# 16_Vibrationdriver.net
KiCad netlist of a schematic drawn in EAGLE
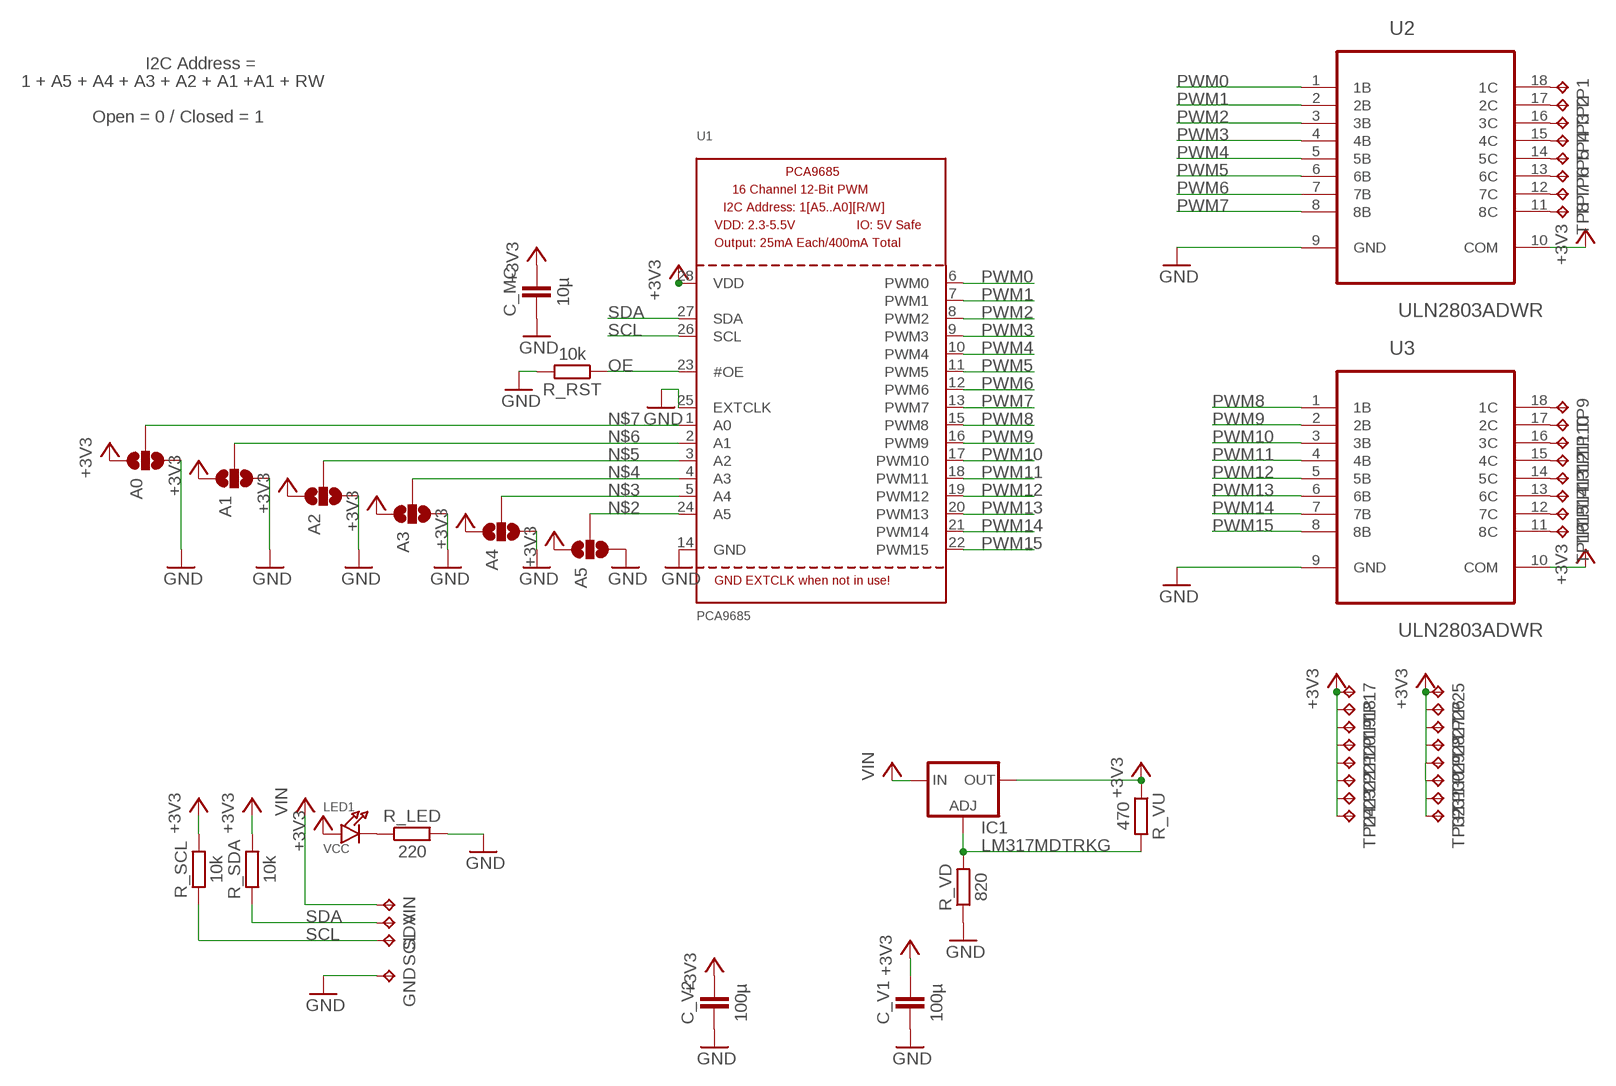
[diagram p0: schematic, sheet 1]

(export (version "E")
  (design (tool "Eeschema 10.0.6"))
  (components
    (comp (ref "A0")
      (value "SOLDERJUMPER_2WAYPASTE2&3")
      (footprint "eagle-import:SJ_3_PASTE2&3")
      (libsource (lib "eagle-import") (part "SOLDERJUMPER_2WAYPASTE2&3"))
    )
    (comp (ref "A1")
      (value "SOLDERJUMPER_2WAYPASTE2&3")
      (footprint "eagle-import:SJ_3_PASTE2&3")
      (libsource (lib "eagle-import") (part "SOLDERJUMPER_2WAYPASTE2&3"))
    )
    (comp (ref "A2")
      (value "SOLDERJUMPER_2WAYPASTE2&3")
      (footprint "eagle-import:SJ_3_PASTE2&3")
      (libsource (lib "eagle-import") (part "SOLDERJUMPER_2WAYPASTE2&3"))
    )
    (comp (ref "A3")
      (value "SOLDERJUMPER_2WAYPASTE2&3")
      (footprint "eagle-import:SJ_3_PASTE2&3")
      (libsource (lib "eagle-import") (part "SOLDERJUMPER_2WAYPASTE2&3"))
    )
    (comp (ref "A4")
      (value "SOLDERJUMPER_2WAYPASTE2&3")
      (footprint "eagle-import:SJ_3_PASTE2&3")
      (libsource (lib "eagle-import") (part "SOLDERJUMPER_2WAYPASTE2&3"))
    )
    (comp (ref "A5")
      (value "SOLDERJUMPER_2WAYPASTE2&3")
      (footprint "eagle-import:SJ_3_PASTE2&3")
      (libsource (lib "eagle-import") (part "SOLDERJUMPER_2WAYPASTE2&3"))
    )
    (comp (ref "C_MC")
      (value "10µ")
      (footprint "eagle-import:603")
      (libsource (lib "eagle-import") (part "CAPACITOR"))
    )
    (comp (ref "C_V1")
      (value "100µ")
      (footprint "eagle-import:1206")
      (libsource (lib "eagle-import") (part "CAPACITOR1206"))
    )
    (comp (ref "C_V2")
      (value "100µ")
      (footprint "eagle-import:1206")
      (libsource (lib "eagle-import") (part "CAPACITOR1206"))
    )
    (comp (ref "GND")
      (value "TPTP16SQ")
      (footprint "eagle-import:TP16SQ")
      (libsource (lib "eagle-import") (part "TPTP16SQ"))
    )
    (comp (ref "IC1")
      (value "LM317MDTRKG")
      (footprint "eagle-import:DPACK")
      (libsource (lib "eagle-import") (part "LM317?MDTRKG"))
    )
    (comp (ref "LED1")
      (value "VCC")
      (footprint "eagle-import:CHIPLED_0805")
      (libsource (lib "eagle-import") (part "LED0805"))
    )
    (comp (ref "R_LED")
      (value "220")
      (footprint "eagle-import:603")
      (libsource (lib "eagle-import") (part "RESISTOR0603"))
    )
    (comp (ref "R_RST")
      (value "10k")
      (footprint "eagle-import:603")
      (libsource (lib "eagle-import") (part "RESISTOR0603"))
    )
    (comp (ref "R_SCL")
      (value "10k")
      (footprint "eagle-import:603")
      (libsource (lib "eagle-import") (part "RESISTOR0603"))
    )
    (comp (ref "R_SDA")
      (value "10k")
      (footprint "eagle-import:603")
      (libsource (lib "eagle-import") (part "RESISTOR0603"))
    )
    (comp (ref "R_VD")
      (value "820")
      (footprint "eagle-import:603")
      (libsource (lib "eagle-import") (part "RESISTOR0603"))
    )
    (comp (ref "R_VU")
      (value "470")
      (footprint "eagle-import:603")
      (libsource (lib "eagle-import") (part "RESISTOR0603"))
    )
    (comp (ref "SCL")
      (value "TPTP16SQ")
      (footprint "eagle-import:TP16SQ")
      (libsource (lib "eagle-import") (part "TPTP16SQ"))
    )
    (comp (ref "SDA")
      (value "TPTP16SQ")
      (footprint "eagle-import:TP16SQ")
      (libsource (lib "eagle-import") (part "TPTP16SQ"))
    )
    (comp (ref "TP1")
      (value "TPTP16SQ")
      (footprint "eagle-import:TP16SQ")
      (libsource (lib "eagle-import") (part "TPTP16SQ"))
    )
    (comp (ref "TP2")
      (value "TPTP16SQ")
      (footprint "eagle-import:TP16SQ")
      (libsource (lib "eagle-import") (part "TPTP16SQ"))
    )
    (comp (ref "TP3")
      (value "TPTP16SQ")
      (footprint "eagle-import:TP16SQ")
      (libsource (lib "eagle-import") (part "TPTP16SQ"))
    )
    (comp (ref "TP4")
      (value "TPTP16SQ")
      (footprint "eagle-import:TP16SQ")
      (libsource (lib "eagle-import") (part "TPTP16SQ"))
    )
    (comp (ref "TP5")
      (value "TPTP16SQ")
      (footprint "eagle-import:TP16SQ")
      (libsource (lib "eagle-import") (part "TPTP16SQ"))
    )
    (comp (ref "TP6")
      (value "TPTP16SQ")
      (footprint "eagle-import:TP16SQ")
      (libsource (lib "eagle-import") (part "TPTP16SQ"))
    )
    (comp (ref "TP7")
      (value "TPTP16SQ")
      (footprint "eagle-import:TP16SQ")
      (libsource (lib "eagle-import") (part "TPTP16SQ"))
    )
    (comp (ref "TP8")
      (value "TPTP16SQ")
      (footprint "eagle-import:TP16SQ")
      (libsource (lib "eagle-import") (part "TPTP16SQ"))
    )
    (comp (ref "TP9")
      (value "TPTP16SQ")
      (footprint "eagle-import:TP16SQ")
      (libsource (lib "eagle-import") (part "TPTP16SQ"))
    )
    (comp (ref "TP10")
      (value "TPTP16SQ")
      (footprint "eagle-import:TP16SQ")
      (libsource (lib "eagle-import") (part "TPTP16SQ"))
    )
    (comp (ref "TP11")
      (value "TPTP16SQ")
      (footprint "eagle-import:TP16SQ")
      (libsource (lib "eagle-import") (part "TPTP16SQ"))
    )
    (comp (ref "TP12")
      (value "TPTP16SQ")
      (footprint "eagle-import:TP16SQ")
      (libsource (lib "eagle-import") (part "TPTP16SQ"))
    )
    (comp (ref "TP13")
      (value "TPTP16SQ")
      (footprint "eagle-import:TP16SQ")
      (libsource (lib "eagle-import") (part "TPTP16SQ"))
    )
    (comp (ref "TP14")
      (value "TPTP16SQ")
      (footprint "eagle-import:TP16SQ")
      (libsource (lib "eagle-import") (part "TPTP16SQ"))
    )
    (comp (ref "TP15")
      (value "TPTP16SQ")
      (footprint "eagle-import:TP16SQ")
      (libsource (lib "eagle-import") (part "TPTP16SQ"))
    )
    (comp (ref "TP16")
      (value "TPTP16SQ")
      (footprint "eagle-import:TP16SQ")
      (libsource (lib "eagle-import") (part "TPTP16SQ"))
    )
    (comp (ref "TP17")
      (value "TPTP16SQ")
      (footprint "eagle-import:TP16SQ")
      (libsource (lib "eagle-import") (part "TPTP16SQ"))
    )
    (comp (ref "TP18")
      (value "TPTP16SQ")
      (footprint "eagle-import:TP16SQ")
      (libsource (lib "eagle-import") (part "TPTP16SQ"))
    )
    (comp (ref "TP19")
      (value "TPTP16SQ")
      (footprint "eagle-import:TP16SQ")
      (libsource (lib "eagle-import") (part "TPTP16SQ"))
    )
    (comp (ref "TP20")
      (value "TPTP16SQ")
      (footprint "eagle-import:TP16SQ")
      (libsource (lib "eagle-import") (part "TPTP16SQ"))
    )
    (comp (ref "TP21")
      (value "TPTP16SQ")
      (footprint "eagle-import:TP16SQ")
      (libsource (lib "eagle-import") (part "TPTP16SQ"))
    )
    (comp (ref "TP22")
      (value "TPTP16SQ")
      (footprint "eagle-import:TP16SQ")
      (libsource (lib "eagle-import") (part "TPTP16SQ"))
    )
    (comp (ref "TP23")
      (value "TPTP16SQ")
      (footprint "eagle-import:TP16SQ")
      (libsource (lib "eagle-import") (part "TPTP16SQ"))
    )
    (comp (ref "TP24")
      (value "TPTP16SQ")
      (footprint "eagle-import:TP16SQ")
      (libsource (lib "eagle-import") (part "TPTP16SQ"))
    )
    (comp (ref "TP25")
      (value "TPTP16SQ")
      (footprint "eagle-import:TP16SQ")
      (libsource (lib "eagle-import") (part "TPTP16SQ"))
    )
    (comp (ref "TP26")
      (value "TPTP16SQ")
      (footprint "eagle-import:TP16SQ")
      (libsource (lib "eagle-import") (part "TPTP16SQ"))
    )
    (comp (ref "TP27")
      (value "TPTP16SQ")
      (footprint "eagle-import:TP16SQ")
      (libsource (lib "eagle-import") (part "TPTP16SQ"))
    )
    (comp (ref "TP28")
      (value "TPTP16SQ")
      (footprint "eagle-import:TP16SQ")
      (libsource (lib "eagle-import") (part "TPTP16SQ"))
    )
    (comp (ref "TP29")
      (value "TPTP16SQ")
      (footprint "eagle-import:TP16SQ")
      (libsource (lib "eagle-import") (part "TPTP16SQ"))
    )
    (comp (ref "TP30")
      (value "TPTP16SQ")
      (footprint "eagle-import:TP16SQ")
      (libsource (lib "eagle-import") (part "TPTP16SQ"))
    )
    (comp (ref "TP31")
      (value "TPTP16SQ")
      (footprint "eagle-import:TP16SQ")
      (libsource (lib "eagle-import") (part "TPTP16SQ"))
    )
    (comp (ref "TP32")
      (value "TPTP16SQ")
      (footprint "eagle-import:TP16SQ")
      (libsource (lib "eagle-import") (part "TPTP16SQ"))
    )
    (comp (ref "U1")
      (value "PCA9685")
      (footprint "eagle-import:TSSOP28")
      (libsource (lib "eagle-import") (part "PCA9685"))
    )
    (comp (ref "U2")
      (value "ULN2803ADWR")
      (footprint "eagle-import:SOIC127P1030X265-18N")
      (libsource (lib "eagle-import") (part "ULN2803ADWR"))
    )
    (comp (ref "U3")
      (value "ULN2803ADWR")
      (footprint "eagle-import:SOIC127P1030X265-18N")
      (libsource (lib "eagle-import") (part "ULN2803ADWR"))
    )
    (comp (ref "VIN")
      (value "TPTP16SQ")
      (footprint "eagle-import:TP16SQ")
      (libsource (lib "eagle-import") (part "TPTP16SQ"))
    )
  )
  (nets
    (net (code "1") (name "+3V3") (class "Default")
      (node (ref "A0") (pin "1") (pinfunction "1_1") (pintype "passive"))
      (node (ref "A1") (pin "1") (pinfunction "1_1") (pintype "passive"))
      (node (ref "A2") (pin "1") (pinfunction "1_1") (pintype "passive"))
      (node (ref "A3") (pin "1") (pinfunction "1_1") (pintype "passive"))
      (node (ref "A4") (pin "1") (pinfunction "1_1") (pintype "passive"))
      (node (ref "A5") (pin "1") (pinfunction "1_1") (pintype "passive"))
      (node (ref "C_MC") (pin "2") (pinfunction "2_2") (pintype "passive"))
      (node (ref "C_V1") (pin "2") (pinfunction "2_2") (pintype "passive"))
      (node (ref "C_V2") (pin "2") (pinfunction "2_2") (pintype "passive"))
      (node (ref "IC1") (pin "4") (pinfunction "OUT_4") (pintype "passive"))
      (node (ref "LED1") (pin "A") (pinfunction "A_A") (pintype "passive"))
      (node (ref "R_SCL") (pin "2") (pinfunction "2_2") (pintype "passive"))
      (node (ref "R_SDA") (pin "2") (pinfunction "2_2") (pintype "passive"))
      (node (ref "R_VU") (pin "1") (pinfunction "1_1") (pintype "passive"))
      (node (ref "TP17") (pin "TP") (pinfunction "TP_TP") (pintype "input"))
      (node (ref "TP18") (pin "TP") (pinfunction "TP_TP") (pintype "input"))
      (node (ref "TP19") (pin "TP") (pinfunction "TP_TP") (pintype "input"))
      (node (ref "TP20") (pin "TP") (pinfunction "TP_TP") (pintype "input"))
      (node (ref "TP21") (pin "TP") (pinfunction "TP_TP") (pintype "input"))
      (node (ref "TP22") (pin "TP") (pinfunction "TP_TP") (pintype "input"))
      (node (ref "TP23") (pin "TP") (pinfunction "TP_TP") (pintype "input"))
      (node (ref "TP24") (pin "TP") (pinfunction "TP_TP") (pintype "input"))
      (node (ref "TP25") (pin "TP") (pinfunction "TP_TP") (pintype "input"))
      (node (ref "TP26") (pin "TP") (pinfunction "TP_TP") (pintype "input"))
      (node (ref "TP27") (pin "TP") (pinfunction "TP_TP") (pintype "input"))
      (node (ref "TP28") (pin "TP") (pinfunction "TP_TP") (pintype "input"))
      (node (ref "TP29") (pin "TP") (pinfunction "TP_TP") (pintype "input"))
      (node (ref "TP30") (pin "TP") (pinfunction "TP_TP") (pintype "input"))
      (node (ref "TP31") (pin "TP") (pinfunction "TP_TP") (pintype "input"))
      (node (ref "TP32") (pin "TP") (pinfunction "TP_TP") (pintype "input"))
      (node (ref "U1") (pin "28") (pinfunction "VDD_28") (pintype "power_in"))
      (node (ref "U2") (pin "10") (pinfunction "COM_10") (pintype "output"))
      (node (ref "U3") (pin "10") (pinfunction "COM_10") (pintype "output"))
    )
    (net (code "2") (name "/N$2") (class "Default")
      (node (ref "A5") (pin "2") (pinfunction "2_2") (pintype "passive"))
      (node (ref "U1") (pin "24") (pinfunction "A5_24") (pintype "bidirectional"))
    )
    (net (code "3") (name "/N$3") (class "Default")
      (node (ref "A4") (pin "2") (pinfunction "2_2") (pintype "passive"))
      (node (ref "U1") (pin "5") (pinfunction "A4_5") (pintype "bidirectional"))
    )
    (net (code "4") (name "/N$4") (class "Default")
      (node (ref "A3") (pin "2") (pinfunction "2_2") (pintype "passive"))
      (node (ref "U1") (pin "4") (pinfunction "A3_4") (pintype "bidirectional"))
    )
    (net (code "5") (name "/N$5") (class "Default")
      (node (ref "A2") (pin "2") (pinfunction "2_2") (pintype "passive"))
      (node (ref "U1") (pin "3") (pinfunction "A2_3") (pintype "bidirectional"))
    )
    (net (code "6") (name "/N$6") (class "Default")
      (node (ref "A1") (pin "2") (pinfunction "2_2") (pintype "passive"))
      (node (ref "U1") (pin "2") (pinfunction "A1_2") (pintype "bidirectional"))
    )
    (net (code "7") (name "/N$7") (class "Default")
      (node (ref "A0") (pin "2") (pinfunction "2_2") (pintype "passive"))
      (node (ref "U1") (pin "1") (pinfunction "A0_1") (pintype "bidirectional"))
    )
    (net (code "8") (name "/OE") (class "Default")
      (node (ref "R_RST") (pin "1") (pinfunction "1_1") (pintype "passive"))
      (node (ref "U1") (pin "23") (pinfunction "#OE_23") (pintype "input"))
    )
    (net (code "9") (name "/PWM0") (class "Default")
      (node (ref "U1") (pin "6") (pinfunction "PWM0_6") (pintype "output"))
      (node (ref "U2") (pin "1") (pinfunction "1B_1") (pintype "input"))
    )
    (net (code "10") (name "/PWM1") (class "Default")
      (node (ref "U1") (pin "7") (pinfunction "PWM1_7") (pintype "output"))
      (node (ref "U2") (pin "2") (pinfunction "2B_2") (pintype "input"))
    )
    (net (code "11") (name "/PWM2") (class "Default")
      (node (ref "U1") (pin "8") (pinfunction "PWM2_8") (pintype "output"))
      (node (ref "U2") (pin "3") (pinfunction "3B_3") (pintype "input"))
    )
    (net (code "12") (name "/PWM3") (class "Default")
      (node (ref "U1") (pin "9") (pinfunction "PWM3_9") (pintype "output"))
      (node (ref "U2") (pin "4") (pinfunction "4B_4") (pintype "input"))
    )
    (net (code "13") (name "/PWM4") (class "Default")
      (node (ref "U1") (pin "10") (pinfunction "PWM4_10") (pintype "output"))
      (node (ref "U2") (pin "5") (pinfunction "5B_5") (pintype "input"))
    )
    (net (code "14") (name "/PWM5") (class "Default")
      (node (ref "U1") (pin "11") (pinfunction "PWM5_11") (pintype "output"))
      (node (ref "U2") (pin "6") (pinfunction "6B_6") (pintype "input"))
    )
    (net (code "15") (name "/PWM6") (class "Default")
      (node (ref "U1") (pin "12") (pinfunction "PWM6_12") (pintype "output"))
      (node (ref "U2") (pin "7") (pinfunction "7B_7") (pintype "input"))
    )
    (net (code "16") (name "/PWM7") (class "Default")
      (node (ref "U1") (pin "13") (pinfunction "PWM7_13") (pintype "output"))
      (node (ref "U2") (pin "8") (pinfunction "8B_8") (pintype "input"))
    )
    (net (code "17") (name "/PWM8") (class "Default")
      (node (ref "U1") (pin "15") (pinfunction "PWM8_15") (pintype "output"))
      (node (ref "U3") (pin "1") (pinfunction "1B_1") (pintype "input"))
    )
    (net (code "18") (name "/PWM9") (class "Default")
      (node (ref "U1") (pin "16") (pinfunction "PWM9_16") (pintype "output"))
      (node (ref "U3") (pin "2") (pinfunction "2B_2") (pintype "input"))
    )
    (net (code "19") (name "/PWM10") (class "Default")
      (node (ref "U1") (pin "17") (pinfunction "PWM10_17") (pintype "output"))
      (node (ref "U3") (pin "3") (pinfunction "3B_3") (pintype "input"))
    )
    (net (code "20") (name "/PWM11") (class "Default")
      (node (ref "U1") (pin "18") (pinfunction "PWM11_18") (pintype "output"))
      (node (ref "U3") (pin "4") (pinfunction "4B_4") (pintype "input"))
    )
    (net (code "21") (name "/PWM12") (class "Default")
      (node (ref "U1") (pin "19") (pinfunction "PWM12_19") (pintype "output"))
      (node (ref "U3") (pin "5") (pinfunction "5B_5") (pintype "input"))
    )
    (net (code "22") (name "/PWM13") (class "Default")
      (node (ref "U1") (pin "20") (pinfunction "PWM13_20") (pintype "output"))
      (node (ref "U3") (pin "6") (pinfunction "6B_6") (pintype "input"))
    )
    (net (code "23") (name "/PWM14") (class "Default")
      (node (ref "U1") (pin "21") (pinfunction "PWM14_21") (pintype "output"))
      (node (ref "U3") (pin "7") (pinfunction "7B_7") (pintype "input"))
    )
    (net (code "24") (name "/PWM15") (class "Default")
      (node (ref "U1") (pin "22") (pinfunction "PWM15_22") (pintype "output"))
      (node (ref "U3") (pin "8") (pinfunction "8B_8") (pintype "input"))
    )
    (net (code "25") (name "/SCL") (class "Default")
      (node (ref "R_SCL") (pin "1") (pinfunction "1_1") (pintype "passive"))
      (node (ref "SCL") (pin "TP") (pinfunction "TP_TP") (pintype "input"))
      (node (ref "U1") (pin "26") (pinfunction "SCL_26") (pintype "bidirectional"))
    )
    (net (code "26") (name "/SDA") (class "Default")
      (node (ref "R_SDA") (pin "1") (pinfunction "1_1") (pintype "passive"))
      (node (ref "SDA") (pin "TP") (pinfunction "TP_TP") (pintype "input"))
      (node (ref "U1") (pin "27") (pinfunction "SDA_27") (pintype "bidirectional"))
    )
    (net (code "27") (name "GND") (class "Default")
      (node (ref "A0") (pin "3") (pinfunction "3_3") (pintype "passive"))
      (node (ref "A1") (pin "3") (pinfunction "3_3") (pintype "passive"))
      (node (ref "A2") (pin "3") (pinfunction "3_3") (pintype "passive"))
      (node (ref "A3") (pin "3") (pinfunction "3_3") (pintype "passive"))
      (node (ref "A4") (pin "3") (pinfunction "3_3") (pintype "passive"))
      (node (ref "A5") (pin "3") (pinfunction "3_3") (pintype "passive"))
      (node (ref "C_MC") (pin "1") (pinfunction "1_1") (pintype "passive"))
      (node (ref "C_V1") (pin "1") (pinfunction "1_1") (pintype "passive"))
      (node (ref "C_V2") (pin "1") (pinfunction "1_1") (pintype "passive"))
      (node (ref "GND") (pin "TP") (pinfunction "TP_TP") (pintype "input"))
      (node (ref "R_LED") (pin "2") (pinfunction "2_2") (pintype "passive"))
      (node (ref "R_RST") (pin "2") (pinfunction "2_2") (pintype "passive"))
      (node (ref "R_VD") (pin "1") (pinfunction "1_1") (pintype "passive"))
      (node (ref "U1") (pin "14") (pinfunction "GND_14") (pintype "power_in"))
      (node (ref "U1") (pin "25") (pinfunction "EXTCLK_25") (pintype "input"))
      (node (ref "U2") (pin "9") (pinfunction "GND_9") (pintype "passive"))
      (node (ref "U3") (pin "9") (pinfunction "GND_9") (pintype "passive"))
    )
    (net (code "28") (name "Net-(IC1-ADJ)") (class "Default")
      (node (ref "IC1") (pin "1") (pinfunction "ADJ_1") (pintype "input"))
      (node (ref "R_VD") (pin "2") (pinfunction "2_2") (pintype "passive"))
      (node (ref "R_VU") (pin "2") (pinfunction "2_2") (pintype "passive"))
    )
    (net (code "29") (name "Net-(LED1-PadC)") (class "Default")
      (node (ref "LED1") (pin "C") (pinfunction "C_C") (pintype "passive"))
      (node (ref "R_LED") (pin "1") (pinfunction "1_1") (pintype "passive"))
    )
    (net (code "30") (name "Net-(U2-1C)") (class "Default")
      (node (ref "TP1") (pin "TP") (pinfunction "TP_TP") (pintype "input"))
      (node (ref "U2") (pin "18") (pinfunction "1C_18") (pintype "output"))
    )
    (net (code "31") (name "Net-(U2-2C)") (class "Default")
      (node (ref "TP2") (pin "TP") (pinfunction "TP_TP") (pintype "input"))
      (node (ref "U2") (pin "17") (pinfunction "2C_17") (pintype "output"))
    )
    (net (code "32") (name "Net-(U2-3C)") (class "Default")
      (node (ref "TP3") (pin "TP") (pinfunction "TP_TP") (pintype "input"))
      (node (ref "U2") (pin "16") (pinfunction "3C_16") (pintype "output"))
    )
    (net (code "33") (name "Net-(U2-4C)") (class "Default")
      (node (ref "TP4") (pin "TP") (pinfunction "TP_TP") (pintype "input"))
      (node (ref "U2") (pin "15") (pinfunction "4C_15") (pintype "output"))
    )
    (net (code "34") (name "Net-(U2-5C)") (class "Default")
      (node (ref "TP5") (pin "TP") (pinfunction "TP_TP") (pintype "input"))
      (node (ref "U2") (pin "14") (pinfunction "5C_14") (pintype "output"))
    )
    (net (code "35") (name "Net-(U2-6C)") (class "Default")
      (node (ref "TP6") (pin "TP") (pinfunction "TP_TP") (pintype "input"))
      (node (ref "U2") (pin "13") (pinfunction "6C_13") (pintype "output"))
    )
    (net (code "36") (name "Net-(U2-7C)") (class "Default")
      (node (ref "TP7") (pin "TP") (pinfunction "TP_TP") (pintype "input"))
      (node (ref "U2") (pin "12") (pinfunction "7C_12") (pintype "output"))
    )
    (net (code "37") (name "Net-(U2-8C)") (class "Default")
      (node (ref "TP8") (pin "TP") (pinfunction "TP_TP") (pintype "input"))
      (node (ref "U2") (pin "11") (pinfunction "8C_11") (pintype "output"))
    )
    (net (code "38") (name "Net-(U3-1C)") (class "Default")
      (node (ref "TP9") (pin "TP") (pinfunction "TP_TP") (pintype "input"))
      (node (ref "U3") (pin "18") (pinfunction "1C_18") (pintype "output"))
    )
    (net (code "39") (name "Net-(U3-2C)") (class "Default")
      (node (ref "TP10") (pin "TP") (pinfunction "TP_TP") (pintype "input"))
      (node (ref "U3") (pin "17") (pinfunction "2C_17") (pintype "output"))
    )
    (net (code "40") (name "Net-(U3-3C)") (class "Default")
      (node (ref "TP11") (pin "TP") (pinfunction "TP_TP") (pintype "input"))
      (node (ref "U3") (pin "16") (pinfunction "3C_16") (pintype "output"))
    )
    (net (code "41") (name "Net-(U3-4C)") (class "Default")
      (node (ref "TP12") (pin "TP") (pinfunction "TP_TP") (pintype "input"))
      (node (ref "U3") (pin "15") (pinfunction "4C_15") (pintype "output"))
    )
    (net (code "42") (name "Net-(U3-5C)") (class "Default")
      (node (ref "TP13") (pin "TP") (pinfunction "TP_TP") (pintype "input"))
      (node (ref "U3") (pin "14") (pinfunction "5C_14") (pintype "output"))
    )
    (net (code "43") (name "Net-(U3-6C)") (class "Default")
      (node (ref "TP14") (pin "TP") (pinfunction "TP_TP") (pintype "input"))
      (node (ref "U3") (pin "13") (pinfunction "6C_13") (pintype "output"))
    )
    (net (code "44") (name "Net-(U3-7C)") (class "Default")
      (node (ref "TP15") (pin "TP") (pinfunction "TP_TP") (pintype "input"))
      (node (ref "U3") (pin "12") (pinfunction "7C_12") (pintype "output"))
    )
    (net (code "45") (name "Net-(U3-8C)") (class "Default")
      (node (ref "TP16") (pin "TP") (pinfunction "TP_TP") (pintype "input"))
      (node (ref "U3") (pin "11") (pinfunction "8C_11") (pintype "output"))
    )
    (net (code "46") (name "VIN") (class "Default")
      (node (ref "IC1") (pin "3") (pinfunction "IN_3") (pintype "input"))
      (node (ref "VIN") (pin "TP") (pinfunction "TP_TP") (pintype "input"))
    )
  )
)
